# voeding.net
KiCad netlist of a schematic drawn in Altium Designer
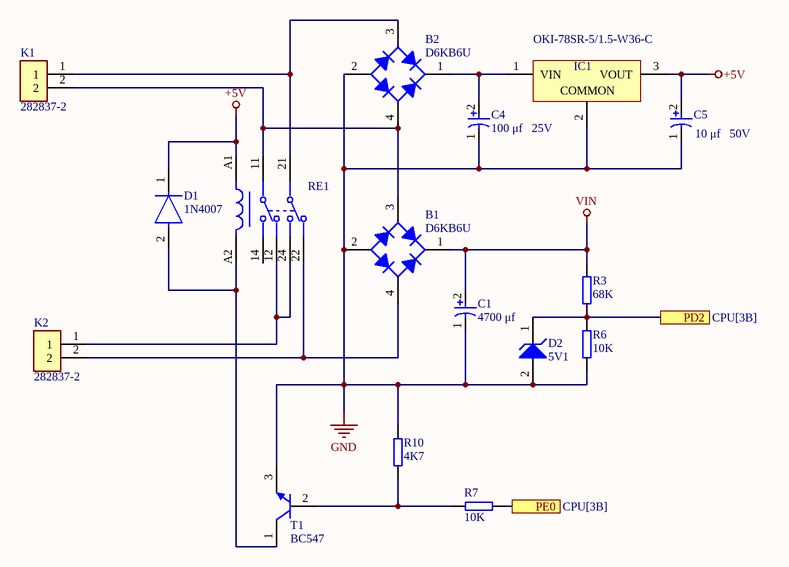
[diagram p0: voeding.SchDoc]

(export (version "E")
  (design (tool "Eeschema 10.0.6"))
  (components
    (comp (ref "B1")
      (value "D6KB6U")
      (footprint "ttf")
      (fields (field (name "MANUFACTURER") "Diodes Inc"))
      (libsource (lib "Soldeerstation_Final") (part "Bridge_Rectifier"))
    )
    (comp (ref "B2")
      (value "D6KB6U")
      (footprint "ttf")
      (fields (field (name "MANUFACTURER") "Diodes Inc"))
      (libsource (lib "Soldeerstation_Final") (part "Bridge_Rectifier"))
    )
    (comp (ref "C1")
      (value "4700 μf")
      (footprint "CE_D8_L10")
      (fields (field (name "MANUFACTURER") "Panasonic"))
      (libsource (lib "Soldeerstation_Final") (part "Capacitor_Electrolytic"))
    )
    (comp (ref "C4")
      (value "100 μf   25V")
      (footprint "CE_D8_L10")
      (fields (field (name "MANUFACTURER") "Panasonic"))
      (libsource (lib "Soldeerstation_Final") (part "Capacitor_Electrolytic"))
    )
    (comp (ref "C5")
      (value "10 μf   50V")
      (footprint "CE_D8_L10")
      (fields (field (name "MANUFACTURER") "Panasonic"))
      (libsource (lib "Soldeerstation_Final") (part "Capacitor_Electrolytic"))
    )
    (comp (ref "D1")
      (value "1N4007")
      (footprint "SOD-123FL")
      (fields
        (field (name "MANUFACTURER") "Diotec")
        (field (name "OCTOPART") "https://octopart.com/1n4007-diotec-4040411")
      )
      (libsource (lib "Soldeerstation_Final") (part "Diode"))
    )
    (comp (ref "D2")
      (value "5V1")
      (footprint "SOD-123FL")
      (fields (field (name "MANUFACTURER") "On Semiconductor") (field (name "PARTNUMBER") "1SMB5920BT3G"))
      (libsource (lib "Soldeerstation_Final") (part "Zener_Diode"))
    )
    (comp (ref "IC1")
      (value "OKI-78SR-5/1.5-W36-C")
      (footprint "OKI78SR515W36C")
      (fields (field (name "MANUFACTURER") "Murata"))
      (libsource (lib "Soldeerstation_Final") (part "DC/DC Converter"))
    )
    (comp (ref "K1")
      (value "282837-2")
      (footprint "TE_282837-2")
      (fields (field (name "MF") "TE Connectivity"))
      (libsource (lib "282837-2") (part "282837-2"))
    )
    (comp (ref "K2")
      (value "282837-2")
      (footprint "TE_282837-2")
      (fields (field (name "MF") "TE Connectivity"))
      (libsource (lib "282837-2") (part "282837-2"))
    )
    (comp (ref "R3")
      (value "68K")
      (footprint "CC_0805_m")
      (fields (field (name "MANUFACTURER") "Vishay Dale") (field (name "PART NUMBER") "CRCW08050000Z0EA"))
      (libsource (lib "Soldeerstation_Final") (part "Resistor"))
    )
    (comp (ref "R6")
      (value "10K")
      (footprint "CC_0805_m")
      (fields (field (name "MANUFACTURER") "Vishay Dale") (field (name "PART NUMBER") "CRCW08050000Z0EA"))
      (libsource (lib "Soldeerstation_Final") (part "Resistor"))
    )
    (comp (ref "R7")
      (value "10K")
      (footprint "CC_0805_m")
      (fields (field (name "MANUFACTURER") "Vishay Dale") (field (name "PART NUMBER") "CRCW08050000Z0EA"))
      (libsource (lib "Soldeerstation_Final") (part "Resistor"))
    )
    (comp (ref "R10")
      (value "4K7")
      (footprint "CC_0805_m")
      (fields (field (name "MANUFACTURER") "Vishay Dale") (field (name "PART NUMBER") "CRCW08050000Z0EA"))
      (libsource (lib "Soldeerstation_Final") (part "Resistor"))
    )
    (comp (ref "RE1")
      (value "~")
      (footprint "RT42")
      (fields
        (field (name "MANUFACTURER PART NUMBER") "RT424005")
        (field (name "OCTOPART") "https://octopart.com/5-1393243-9-te+connectivity-41835766")
        (field (name "MANUFACTURER") "TE Connectivity")
      )
      (libsource (lib "Soldeerstation_Final") (part "RELAY_GENERAL_PURPOSE"))
    )
    (comp (ref "T1")
      (value "BC547")
      (footprint "SOT_23")
      (fields (field (name "MANUFACTURER") "On Semiconductor") (field (name "PARTNUMBER") "BC547C"))
      (libsource (lib "Soldeerstation_Final") (part "Transistor_NPN"))
    )
  )
  (nets
    (net (code "1") (name "+5V") (class "Default")
      (node (ref "C5") (pin "2") (pinfunction "2_2") (pintype "passive"))
      (node (ref "D1") (pin "1") (pinfunction "C_1") (pintype "passive"))
      (node (ref "IC1") (pin "3") (pinfunction "VOUT_3") (pintype "power_in"))
      (node (ref "RE1") (pin "A1") (pinfunction "A1_A1") (pintype "passive"))
    )
    (net (code "2") (name "/PD2") (class "Default")
      (node (ref "D2") (pin "1") (pinfunction "K_1") (pintype "passive"))
      (node (ref "R3") (pin "1") (pinfunction "1_1") (pintype "passive"))
      (node (ref "R6") (pin "2") (pinfunction "2_2") (pintype "passive"))
    )
    (net (code "3") (name "/PE0") (class "Default")
      (node (ref "R7") (pin "1") (pinfunction "1_1") (pintype "passive"))
    )
    (net (code "4") (name "GND") (class "Default")
      (node (ref "B1") (pin "2") (pinfunction "A_2") (pintype "passive"))
      (node (ref "B2") (pin "2") (pinfunction "A_2") (pintype "passive"))
      (node (ref "C1") (pin "1") (pinfunction "1_1") (pintype "passive"))
      (node (ref "C4") (pin "1") (pinfunction "1_1") (pintype "passive"))
      (node (ref "C5") (pin "1") (pinfunction "1_1") (pintype "passive"))
      (node (ref "D2") (pin "2") (pinfunction "A_2") (pintype "passive"))
      (node (ref "IC1") (pin "2") (pinfunction "COMMON_2") (pintype "power_in"))
      (node (ref "R10") (pin "2") (pinfunction "2_2") (pintype "passive"))
      (node (ref "R6") (pin "1") (pinfunction "1_1") (pintype "passive"))
      (node (ref "T1") (pin "3") (pinfunction "E_3") (pintype "passive"))
    )
    (net (code "5") (name "Net-(B1-C-Pad3)") (class "Default")
      (node (ref "B1") (pin "3") (pinfunction "C_3") (pintype "passive"))
      (node (ref "B2") (pin "4") (pinfunction "C_4") (pintype "passive"))
      (node (ref "K1") (pin "2") (pinfunction "2_2") (pintype "passive"))
      (node (ref "RE1") (pin "11") (pinfunction "11_11") (pintype "passive"))
    )
    (net (code "6") (name "Net-(B1-C-Pad4)") (class "Default")
      (node (ref "B1") (pin "4") (pinfunction "C_4") (pintype "passive"))
      (node (ref "K2") (pin "2") (pinfunction "2_2") (pintype "passive"))
      (node (ref "RE1") (pin "22") (pinfunction "22_22") (pintype "passive"))
    )
    (net (code "7") (name "Net-(B2-C-Pad3)") (class "Default")
      (node (ref "B2") (pin "3") (pinfunction "C_3") (pintype "passive"))
      (node (ref "K1") (pin "1") (pinfunction "1_1") (pintype "passive"))
      (node (ref "RE1") (pin "21") (pinfunction "21_21") (pintype "passive"))
    )
    (net (code "8") (name "Net-(B2-K)") (class "Default")
      (node (ref "B2") (pin "1") (pinfunction "K_1") (pintype "passive"))
      (node (ref "C4") (pin "2") (pinfunction "2_2") (pintype "passive"))
      (node (ref "IC1") (pin "1") (pinfunction "VIN_1") (pintype "power_in"))
    )
    (net (code "9") (name "Net-(D1-A)") (class "Default")
      (node (ref "D1") (pin "2") (pinfunction "A_2") (pintype "passive"))
      (node (ref "RE1") (pin "A2") (pinfunction "A2_A2") (pintype "passive"))
      (node (ref "T1") (pin "1") (pinfunction "C_1") (pintype "passive"))
    )
    (net (code "10") (name "Net-(K2-Pad1)") (class "Default")
      (node (ref "K2") (pin "1") (pinfunction "1_1") (pintype "passive"))
      (node (ref "RE1") (pin "12") (pinfunction "12_12") (pintype "passive"))
      (node (ref "RE1") (pin "24") (pinfunction "24_24") (pintype "passive"))
    )
    (net (code "11") (name "Net-(T1-B)") (class "Default")
      (node (ref "R10") (pin "1") (pinfunction "1_1") (pintype "passive"))
      (node (ref "R7") (pin "2") (pinfunction "2_2") (pintype "passive"))
      (node (ref "T1") (pin "2") (pinfunction "B_2") (pintype "passive"))
    )
    (net (code "12") (name "VIN") (class "Default")
      (node (ref "B1") (pin "1") (pinfunction "K_1") (pintype "passive"))
      (node (ref "C1") (pin "2") (pinfunction "2_2") (pintype "passive"))
      (node (ref "R3") (pin "2") (pinfunction "2_2") (pintype "passive"))
    )
    (net (code "13") (name "unconnected-(RE1-Pad14)") (class "Default")
      (node (ref "RE1") (pin "14") (pinfunction "14_14") (pintype "passive"))
    )
  )
)
